# 02-USER_IO.net
KiCad netlist of a schematic drawn in Altium Designer
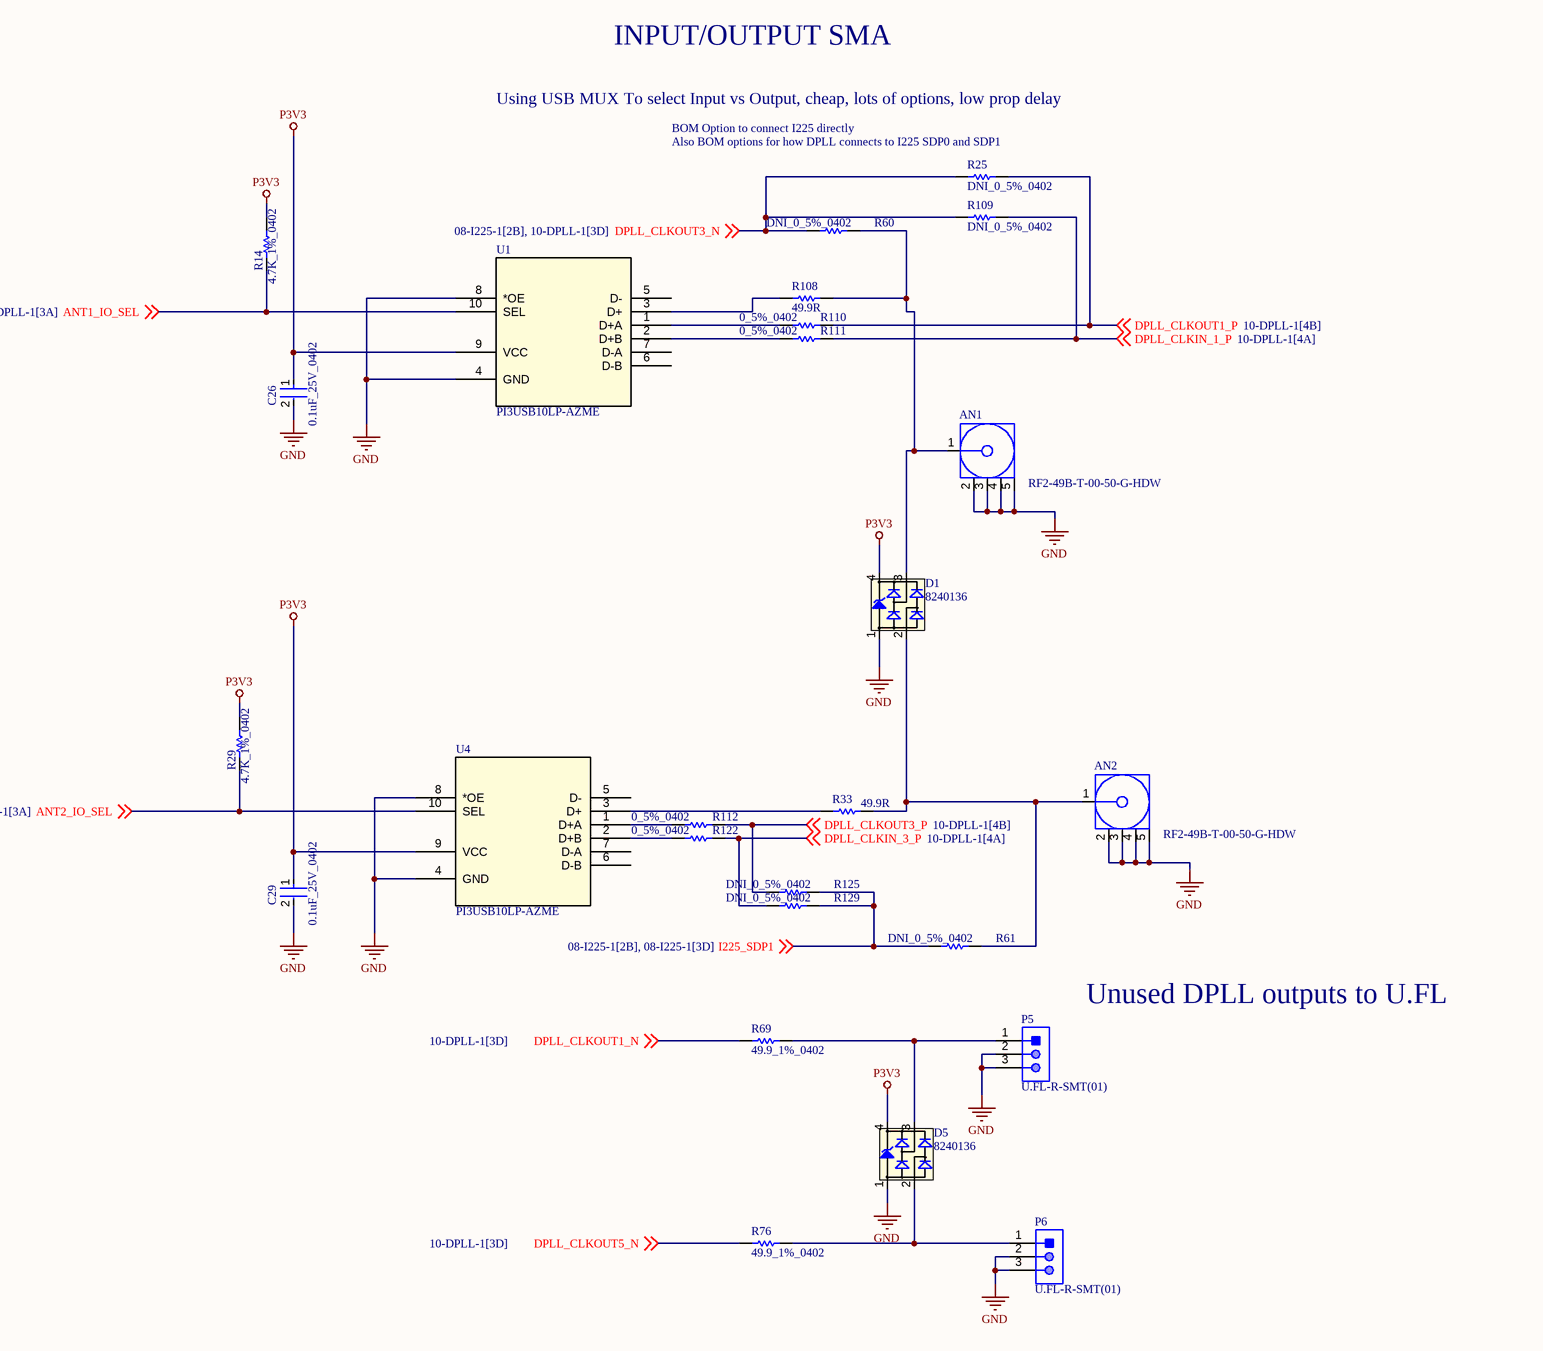
[diagram p0: 02-USER_IO.SchDoc]

(export (version "E")
  (design (tool "Eeschema 10.0.6"))
  (components
    (comp (ref "AN1")
      (value "RF2-49B-T-00-50-G-HDW")
      (footprint "AMPH-901-143-6RFX_V")
      (description "Coaxial connector, 50 Ohm, -65 to 165 degC, 5-Pin THD, RoHS, Bulk")
      (fields (field (name "MANUFACTURER") "Amphenol"))
      (libsource (lib "Altium Content Vault") (part "CN-S-4F-RF5"))
    )
    (comp (ref "AN2")
      (value "RF2-49B-T-00-50-G-HDW")
      (footprint "AMPH-901-143-6RFX_V")
      (description "Coaxial connector, 50 Ohm, -65 to 165 degC, 5-Pin THD, RoHS, Bulk")
      (fields (field (name "MANUFACTURER") "Amphenol"))
      (libsource (lib "Altium Content Vault") (part "CN-S-4F-RF5"))
    )
    (comp (ref "C26")
      (value "0.1uF_25V_0402")
      (footprint "FP-0402-L_1_0_1-W_0_5_0_1-IPC_C")
      (description "General Purpose Ceramic Capacitor, 0402, 100nF, 10%, X7R, 15%, 25V")
      (fields (field (name "VOLTAGE") "25V") (field (name "TOLERANCE") "10%"))
      (libsource (lib "Altium Content Vault") (part "b4654b650e69147ec39a6b967a45e02"))
    )
    (comp (ref "C29")
      (value "0.1uF_25V_0402")
      (footprint "FP-0402-L_1_0_1-W_0_5_0_1-IPC_C")
      (description "General Purpose Ceramic Capacitor, 0402, 100nF, 10%, X7R, 15%, 25V")
      (fields (field (name "VOLTAGE") "25V") (field (name "TOLERANCE") "10%"))
      (libsource (lib "Altium Content Vault") (part "b4654b650e69147ec39a6b967a45e02"))
    )
    (comp (ref "D1")
      (value "8240136")
      (footprint "SOT143-4L")
      (description "TVS Diode WE-TVS-HS, VRWM=3.3V")
      (fields (field (name "MANUFACTURER") "Wuerth Elektronik"))
      (libsource (lib "Altium Content Vault") (part "WE-TVS-HS-4"))
    )
    (comp (ref "D5")
      (value "8240136")
      (footprint "SOT143-4L")
      (description "TVS Diode WE-TVS-HS, VRWM=3.3V")
      (fields (field (name "MANUFACTURER") "Wuerth Elektronik"))
      (libsource (lib "Altium Content Vault") (part "WE-TVS-HS-4"))
    )
    (comp (ref "P5")
      (value "U.FL-R-SMT(01)")
      (footprint "HRS-U.FL-R-SMT(10)_V")
      (description "CONN RECPT ULTRA-MINI COAX SMD")
      (fields (field (name "MANUFACTURER") "Hirose Electric") (field (name "APPROVAL CATEGORY") "UL94V-0"))
      (libsource (lib "Altium Content Vault") (part "CN-1P-M-R3"))
    )
    (comp (ref "P6")
      (value "U.FL-R-SMT(01)")
      (footprint "HRS-U.FL-R-SMT(10)_V")
      (description "CONN RECPT ULTRA-MINI COAX SMD")
      (fields (field (name "MANUFACTURER") "Hirose Electric") (field (name "APPROVAL CATEGORY") "UL94V-0"))
      (libsource (lib "Altium Content Vault") (part "CN-1P-M-R3"))
    )
    (comp (ref "R14")
      (value "4.7K_1%_0402")
      (footprint "RESC1005X40X25NL10T10")
      (fields (field (name "MANUFACTURER") "Bourns") (field (name "PART NUMBER") "CR0402-FX-4701GLF"))
      (libsource (lib "Altium Content Vault") (part "RES"))
    )
    (comp (ref "R25")
      (value "DNI_0_5%_0402")
      (footprint "RESC1005X40X25LL10T10")
      (fields (field (name "MANUFACTURER") "KOA Speer") (field (name "PART NUMBER") "RK73Z1ETTP"))
      (libsource (lib "Altium Content Vault") (part "RES"))
    )
    (comp (ref "R29")
      (value "4.7K_1%_0402")
      (footprint "RESC1005X40X25NL10T10")
      (fields (field (name "MANUFACTURER") "Bourns") (field (name "PART NUMBER") "CR0402-FX-4701GLF"))
      (libsource (lib "Altium Content Vault") (part "RES"))
    )
    (comp (ref "R33")
      (value "49.9R")
      (footprint "RESC1608X55X25NL10T15")
      (libsource (lib "Altium Content Vault") (part "RES-2"))
    )
    (comp (ref "R60")
      (value "DNI_0_5%_0402")
      (footprint "RESC1005X40X25LL10T10")
      (fields (field (name "MANUFACTURER") "KOA Speer") (field (name "PART NUMBER") "RK73Z1ETTP"))
      (libsource (lib "Altium Content Vault") (part "RES"))
    )
    (comp (ref "R61")
      (value "DNI_0_5%_0402")
      (footprint "RESC1005X40X25LL10T10")
      (fields (field (name "MANUFACTURER") "KOA Speer") (field (name "PART NUMBER") "RK73Z1ETTP"))
      (libsource (lib "Altium Content Vault") (part "RES"))
    )
    (comp (ref "R69")
      (value "49.9_1%_0402")
      (footprint "RESC1005X40X25NL10T10")
      (fields (field (name "PART NUMBER") "RK73H1ETTP49R9F") (field (name "MANUFACTURER") "KOA Speer"))
      (libsource (lib "Altium Content Vault") (part "RES"))
    )
    (comp (ref "R76")
      (value "49.9_1%_0402")
      (footprint "RESC1005X40X25NL10T10")
      (fields (field (name "PART NUMBER") "RK73H1ETTP49R9F") (field (name "MANUFACTURER") "KOA Speer"))
      (libsource (lib "Altium Content Vault") (part "RES"))
    )
    (comp (ref "R108")
      (value "49.9R")
      (footprint "RESC1608X55X25NL10T15")
      (libsource (lib "Altium Content Vault") (part "RES-2"))
    )
    (comp (ref "R109")
      (value "DNI_0_5%_0402")
      (footprint "RESC1005X40X25LL10T10")
      (fields (field (name "MANUFACTURER") "KOA Speer") (field (name "PART NUMBER") "RK73Z1ETTP"))
      (libsource (lib "Altium Content Vault") (part "RES"))
    )
    (comp (ref "R110")
      (value "0_5%_0402")
      (footprint "RESC1005X40X25LL10T10")
      (fields (field (name "MANUFACTURER") "KOA Speer") (field (name "PART NUMBER") "RK73Z1ETTP"))
      (libsource (lib "Altium Content Vault") (part "RES"))
    )
    (comp (ref "R111")
      (value "0_5%_0402")
      (footprint "RESC1005X40X25LL10T10")
      (fields (field (name "MANUFACTURER") "KOA Speer") (field (name "PART NUMBER") "RK73Z1ETTP"))
      (libsource (lib "Altium Content Vault") (part "RES"))
    )
    (comp (ref "R112")
      (value "0_5%_0402")
      (footprint "RESC1005X40X25LL10T10")
      (fields (field (name "MANUFACTURER") "KOA Speer") (field (name "PART NUMBER") "RK73Z1ETTP"))
      (libsource (lib "Altium Content Vault") (part "RES"))
    )
    (comp (ref "R122")
      (value "0_5%_0402")
      (footprint "RESC1005X40X25LL10T10")
      (fields (field (name "MANUFACTURER") "KOA Speer") (field (name "PART NUMBER") "RK73Z1ETTP"))
      (libsource (lib "Altium Content Vault") (part "RES"))
    )
    (comp (ref "R125")
      (value "DNI_0_5%_0402")
      (footprint "RESC1005X40X25LL10T10")
      (fields (field (name "MANUFACTURER") "KOA Speer") (field (name "PART NUMBER") "RK73Z1ETTP"))
      (libsource (lib "Altium Content Vault") (part "RES"))
    )
    (comp (ref "R129")
      (value "DNI_0_5%_0402")
      (footprint "RESC1005X40X25LL10T10")
      (fields (field (name "MANUFACTURER") "KOA Speer") (field (name "PART NUMBER") "RK73Z1ETTP"))
      (libsource (lib "Altium Content Vault") (part "RES"))
    )
    (comp (ref "U1")
      (value "PI3USB10LP-AZME")
      (footprint "ZM10_PER")
      (description "No Description Available")
      (libsource (lib "PI3USB10LP-AZME") (part "PI3USB10LP-AZME"))
    )
    (comp (ref "U4")
      (value "PI3USB10LP-AZME")
      (footprint "ZM10_PER")
      (description "No Description Available")
      (libsource (lib "PI3USB10LP-AZME") (part "PI3USB10LP-AZME"))
    )
  )
  (nets
    (net (code "1") (name "ANT1_IO_SEL") (class "Default")
      (node (ref "R14") (pin "2") (pinfunction "2_2") (pintype "passive"))
      (node (ref "U1") (pin "10") (pinfunction "SEL_10") (pintype "passive"))
    )
    (net (code "2") (name "ANT2_IO_SEL") (class "Default")
      (node (ref "R29") (pin "2") (pinfunction "2_2") (pintype "passive"))
      (node (ref "U4") (pin "10") (pinfunction "SEL_10") (pintype "passive"))
    )
    (net (code "3") (name "DPLL_CLKIN_1_P") (class "Default")
      (node (ref "R109") (pin "1") (pinfunction "1_1") (pintype "passive"))
      (node (ref "R111") (pin "2") (pinfunction "2_2") (pintype "passive"))
    )
    (net (code "4") (name "DPLL_CLKIN_3_P") (class "Default")
      (node (ref "R122") (pin "2") (pinfunction "2_2") (pintype "passive"))
      (node (ref "R129") (pin "1") (pinfunction "1_1") (pintype "passive"))
    )
    (net (code "5") (name "DPLL_CLKOUT1_N") (class "Default")
      (node (ref "R69") (pin "1") (pinfunction "1_1") (pintype "passive"))
    )
    (net (code "6") (name "DPLL_CLKOUT1_P") (class "Default")
      (node (ref "R110") (pin "2") (pinfunction "2_2") (pintype "passive"))
      (node (ref "R25") (pin "1") (pinfunction "1_1") (pintype "passive"))
    )
    (net (code "7") (name "DPLL_CLKOUT3_N") (class "Default")
      (node (ref "R109") (pin "2") (pinfunction "2_2") (pintype "passive"))
      (node (ref "R25") (pin "2") (pinfunction "2_2") (pintype "passive"))
      (node (ref "R60") (pin "1") (pinfunction "1_1") (pintype "passive"))
    )
    (net (code "8") (name "DPLL_CLKOUT3_P") (class "Default")
      (node (ref "R112") (pin "2") (pinfunction "2_2") (pintype "passive"))
      (node (ref "R125") (pin "1") (pinfunction "1_1") (pintype "passive"))
    )
    (net (code "9") (name "DPLL_CLKOUT5_N") (class "Default")
      (node (ref "R76") (pin "1") (pinfunction "1_1") (pintype "passive"))
    )
    (net (code "10") (name "GND") (class "Default")
      (node (ref "AN1") (pin "2") (pinfunction "2_2") (pintype "passive"))
      (node (ref "AN1") (pin "3") (pinfunction "3_3") (pintype "passive"))
      (node (ref "AN1") (pin "4") (pinfunction "4_4") (pintype "passive"))
      (node (ref "AN1") (pin "5") (pinfunction "5_5") (pintype "passive"))
      (node (ref "AN2") (pin "2") (pinfunction "2_2") (pintype "passive"))
      (node (ref "AN2") (pin "3") (pinfunction "3_3") (pintype "passive"))
      (node (ref "AN2") (pin "4") (pinfunction "4_4") (pintype "passive"))
      (node (ref "AN2") (pin "5") (pinfunction "5_5") (pintype "passive"))
      (node (ref "C26") (pin "2") (pinfunction "2_2") (pintype "passive"))
      (node (ref "C29") (pin "2") (pinfunction "2_2") (pintype "passive"))
      (node (ref "D1") (pin "1") (pinfunction "GND_1") (pintype "passive"))
      (node (ref "D5") (pin "1") (pinfunction "GND_1") (pintype "passive"))
      (node (ref "P5") (pin "2") (pinfunction "2_2") (pintype "passive"))
      (node (ref "P5") (pin "3") (pinfunction "3_3") (pintype "passive"))
      (node (ref "P6") (pin "2") (pinfunction "2_2") (pintype "passive"))
      (node (ref "P6") (pin "3") (pinfunction "3_3") (pintype "passive"))
      (node (ref "U1") (pin "4") (pinfunction "GND_4") (pintype "power_in"))
      (node (ref "U1") (pin "8") (pinfunction "*OE_8") (pintype "passive"))
      (node (ref "U4") (pin "4") (pinfunction "GND_4") (pintype "power_in"))
      (node (ref "U4") (pin "8") (pinfunction "*OE_8") (pintype "passive"))
    )
    (net (code "11") (name "I225_SDP1") (class "Default")
      (node (ref "R125") (pin "2") (pinfunction "2_2") (pintype "passive"))
      (node (ref "R129") (pin "2") (pinfunction "2_2") (pintype "passive"))
      (node (ref "R61") (pin "1") (pinfunction "1_1") (pintype "passive"))
    )
    (net (code "12") (name "Net-(D1-I{slash}O1)") (class "Default")
      (node (ref "AN2") (pin "1") (pinfunction "1_1") (pintype "passive"))
      (node (ref "D1") (pin "2") (pinfunction "I/O1_2") (pintype "passive"))
      (node (ref "R33") (pin "2") (pinfunction "2_2") (pintype "passive"))
      (node (ref "R61") (pin "2") (pinfunction "2_2") (pintype "passive"))
    )
    (net (code "13") (name "Net-(D1-I{slash}O2)") (class "Default")
      (node (ref "AN1") (pin "1") (pinfunction "1_1") (pintype "passive"))
      (node (ref "D1") (pin "3") (pinfunction "I/O2_3") (pintype "passive"))
      (node (ref "R108") (pin "1") (pinfunction "1_1") (pintype "passive"))
      (node (ref "R60") (pin "2") (pinfunction "2_2") (pintype "passive"))
    )
    (net (code "14") (name "Net-(D5-I{slash}O1)") (class "Default")
      (node (ref "D5") (pin "2") (pinfunction "I/O1_2") (pintype "passive"))
      (node (ref "P6") (pin "1") (pinfunction "1_1") (pintype "passive"))
      (node (ref "R76") (pin "2") (pinfunction "2_2") (pintype "passive"))
    )
    (net (code "15") (name "Net-(D5-I{slash}O2)") (class "Default")
      (node (ref "D5") (pin "3") (pinfunction "I/O2_3") (pintype "passive"))
      (node (ref "P5") (pin "1") (pinfunction "1_1") (pintype "passive"))
      (node (ref "R69") (pin "2") (pinfunction "2_2") (pintype "passive"))
    )
    (net (code "16") (name "Net-(U1-D+)") (class "Default")
      (node (ref "R108") (pin "2") (pinfunction "2_2") (pintype "passive"))
      (node (ref "U1") (pin "3") (pinfunction "D+_3") (pintype "passive"))
    )
    (net (code "17") (name "Net-(U1-D+A)") (class "Default")
      (node (ref "R110") (pin "1") (pinfunction "1_1") (pintype "passive"))
      (node (ref "U1") (pin "1") (pinfunction "D+A_1") (pintype "passive"))
    )
    (net (code "18") (name "Net-(U1-D+B)") (class "Default")
      (node (ref "R111") (pin "1") (pinfunction "1_1") (pintype "passive"))
      (node (ref "U1") (pin "2") (pinfunction "D+B_2") (pintype "passive"))
    )
    (net (code "19") (name "Net-(U4-D+)") (class "Default")
      (node (ref "R33") (pin "1") (pinfunction "1_1") (pintype "passive"))
      (node (ref "U4") (pin "3") (pinfunction "D+_3") (pintype "passive"))
    )
    (net (code "20") (name "Net-(U4-D+A)") (class "Default")
      (node (ref "R112") (pin "1") (pinfunction "1_1") (pintype "passive"))
      (node (ref "U4") (pin "1") (pinfunction "D+A_1") (pintype "passive"))
    )
    (net (code "21") (name "Net-(U4-D+B)") (class "Default")
      (node (ref "R122") (pin "1") (pinfunction "1_1") (pintype "passive"))
      (node (ref "U4") (pin "2") (pinfunction "D+B_2") (pintype "passive"))
    )
    (net (code "22") (name "P3V3") (class "Default")
      (node (ref "C26") (pin "1") (pinfunction "1_1") (pintype "passive"))
      (node (ref "C29") (pin "1") (pinfunction "1_1") (pintype "passive"))
      (node (ref "D1") (pin "4") (pinfunction "VDD_4") (pintype "passive"))
      (node (ref "D5") (pin "4") (pinfunction "VDD_4") (pintype "passive"))
      (node (ref "R14") (pin "1") (pinfunction "1_1") (pintype "passive"))
      (node (ref "R29") (pin "1") (pinfunction "1_1") (pintype "passive"))
      (node (ref "U1") (pin "9") (pinfunction "VCC_9") (pintype "power_in"))
      (node (ref "U4") (pin "9") (pinfunction "VCC_9") (pintype "power_in"))
    )
    (net (code "23") (name "unconnected-(U1-D--Pad5)") (class "Default")
      (node (ref "U1") (pin "5") (pinfunction "D-_5") (pintype "passive"))
    )
    (net (code "24") (name "unconnected-(U1-D-A-Pad7)") (class "Default")
      (node (ref "U1") (pin "7") (pinfunction "D-A_7") (pintype "passive"))
    )
    (net (code "25") (name "unconnected-(U1-D-B-Pad6)") (class "Default")
      (node (ref "U1") (pin "6") (pinfunction "D-B_6") (pintype "passive"))
    )
    (net (code "26") (name "unconnected-(U4-D--Pad5)") (class "Default")
      (node (ref "U4") (pin "5") (pinfunction "D-_5") (pintype "passive"))
    )
    (net (code "27") (name "unconnected-(U4-D-A-Pad7)") (class "Default")
      (node (ref "U4") (pin "7") (pinfunction "D-A_7") (pintype "passive"))
    )
    (net (code "28") (name "unconnected-(U4-D-B-Pad6)") (class "Default")
      (node (ref "U4") (pin "6") (pinfunction "D-B_6") (pintype "passive"))
    )
  )
)
